# PowerSupply.net
KiCad netlist of a schematic drawn in Altium Designer
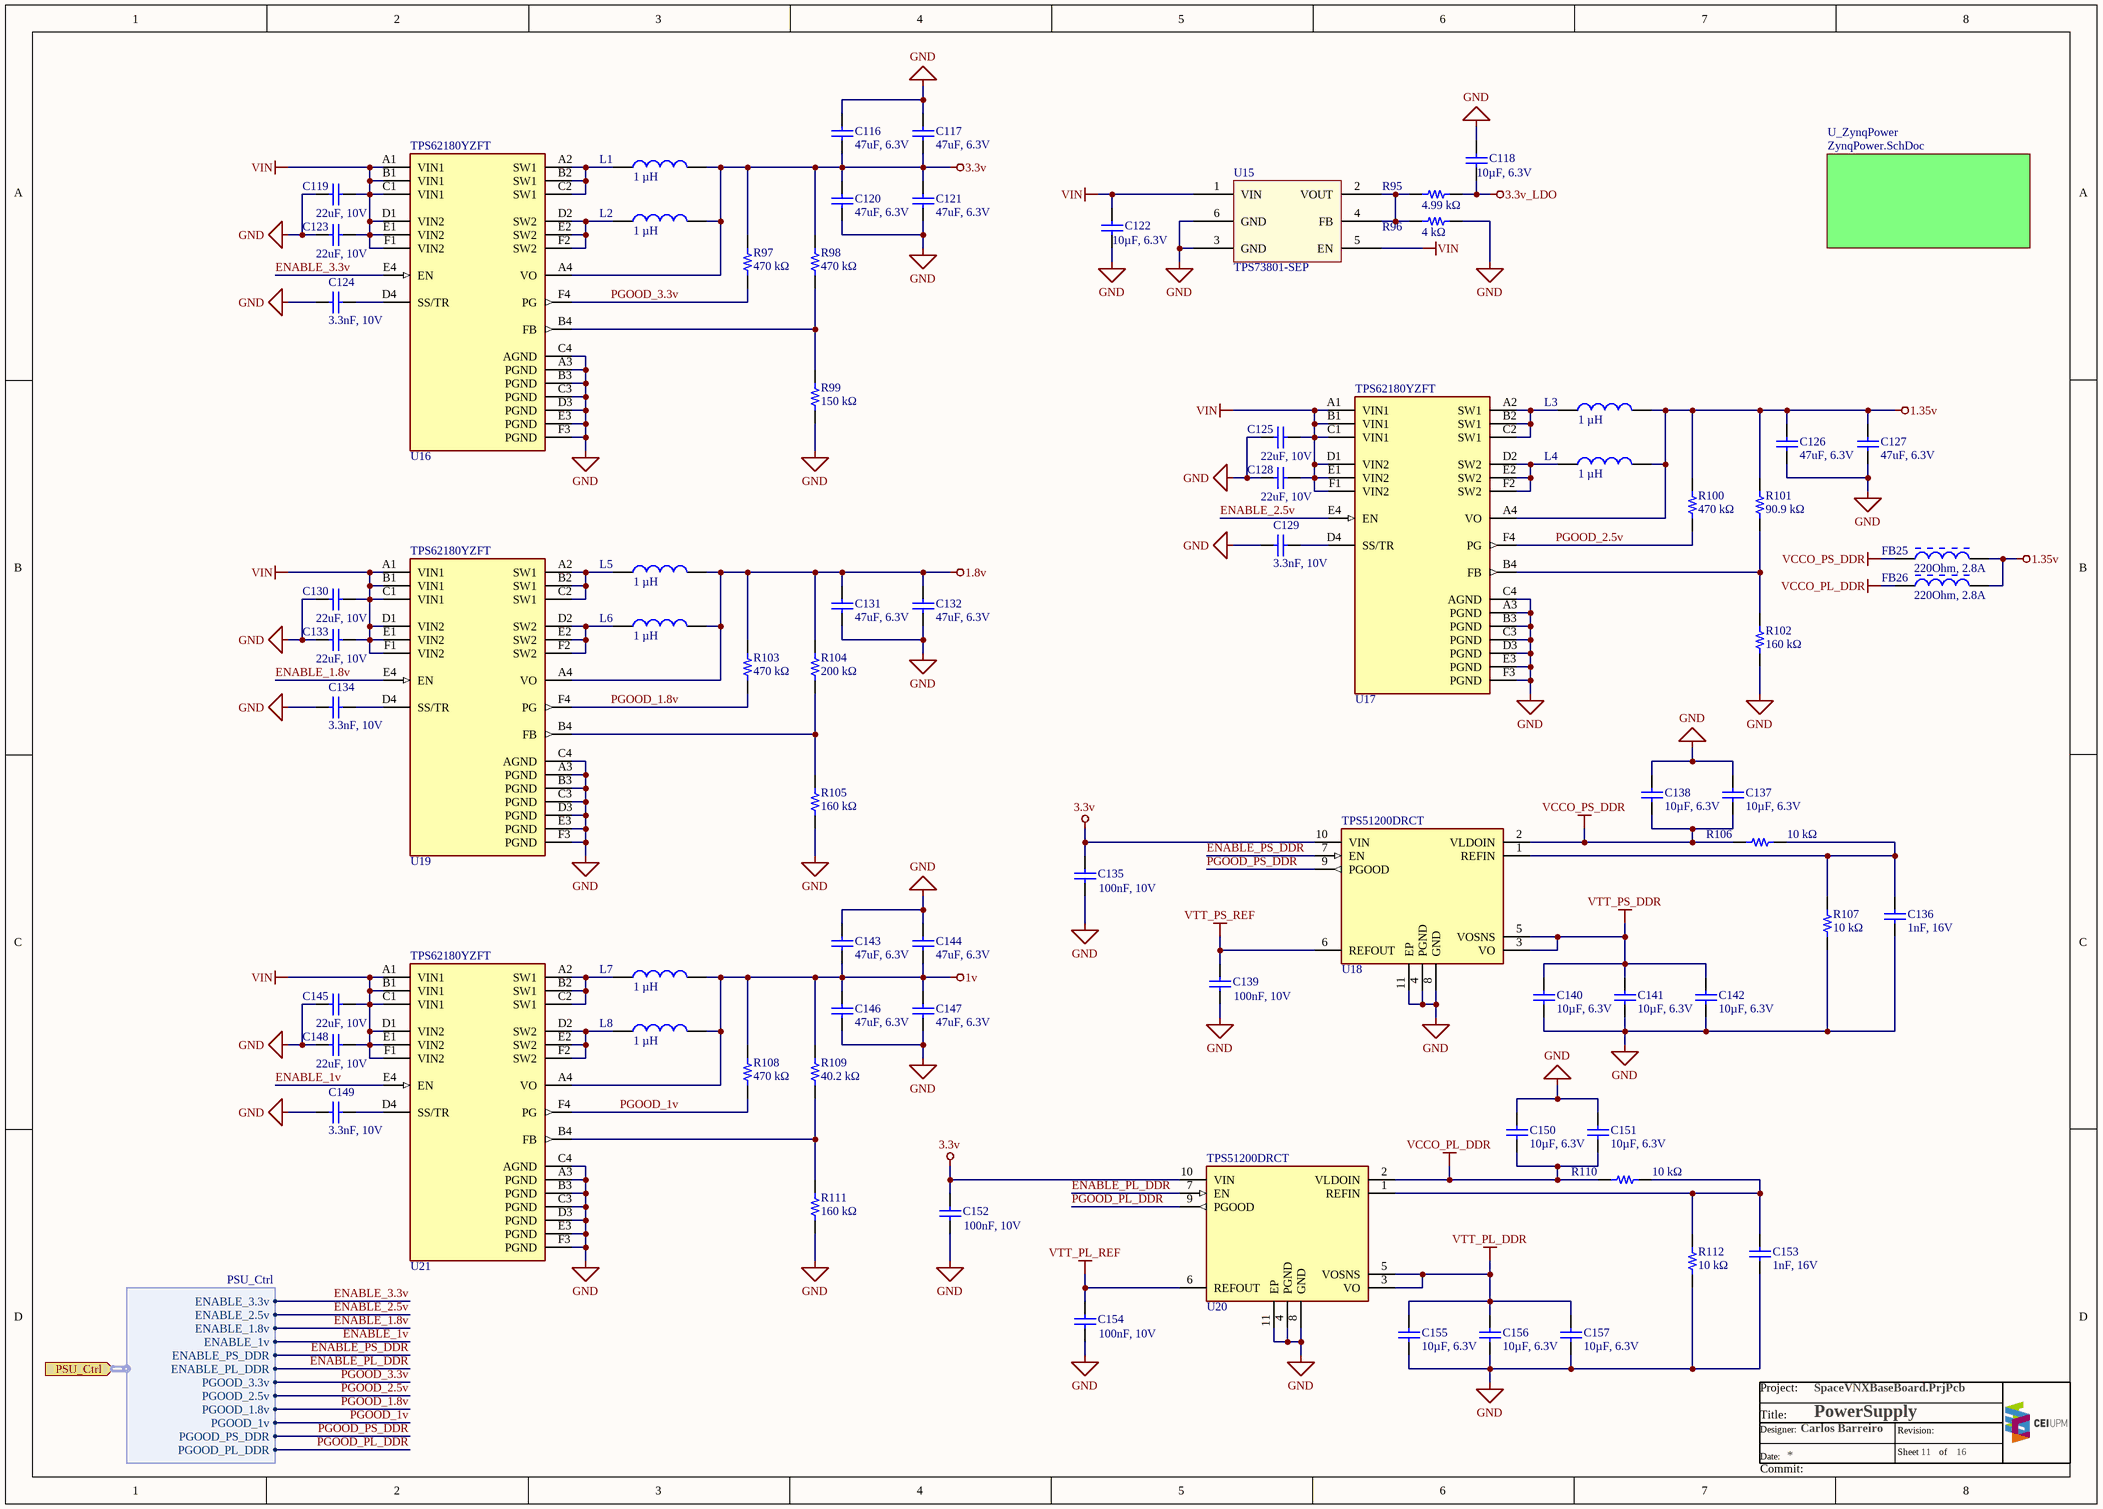
[diagram p0: PowerSupply.SchDoc]

(export (version "E")
  (design (tool "Eeschema 10.0.6"))
  (components
    (comp (ref "C116")
      (value "47uF, 6.3V")
      (footprint "WURTH_WCAP-CSGP_0805_H=1.25mm")
      (description "WCAP-CSGP Multilayer Ceramic Chip Capacitor, General Purpose, size 0805, X5R, 47uF, 6.3V")
      (fields
        (field (name "MANUFACTURER PART NUMBER") "885012107006")
        (field (name "MANUFACTURER") "Wurth Elektronik")
      )
      (libsource (lib "SpaceVNX") (part "885012107006"))
    )
    (comp (ref "C117")
      (value "47uF, 6.3V")
      (footprint "WURTH_WCAP-CSGP_0805_H=1.25mm")
      (description "WCAP-CSGP Multilayer Ceramic Chip Capacitor, General Purpose, size 0805, X5R, 47uF, 6.3V")
      (fields
        (field (name "MANUFACTURER PART NUMBER") "885012107006")
        (field (name "MANUFACTURER") "Wurth Elektronik")
      )
      (libsource (lib "SpaceVNX") (part "885012107006"))
    )
    (comp (ref "C118")
      (value "10µF, 6.3V")
      (footprint "WURTH_WCAP-CSGP_0402")
      (description "WCAP-CSGP Multilayer Ceramic Chip Capacitor, General Purpose, size 0402, X5R, 10uF, 6.3V")
      (fields
        (field (name "MANUFACTURER PART NUMBER") "885012105020")
        (field (name "MANUFACTURER") "Wurth Elektronik")
      )
      (libsource (lib "SpaceVNX") (part "885012105020"))
    )
    (comp (ref "C119")
      (value "22uF, 10V")
      (footprint "WURTH_WCAP-CSGP_0805_H=1.25mm")
      (description "WCAP-CSGP Multilayer Ceramic Chip Capacitor, General Purpose, size 0805, X5R, 22uF, 10V")
      (fields
        (field (name "MANUFACTURER PART NUMBER") "885012107011")
        (field (name "MANUFACTURER") "Wurth Elektronik")
      )
      (libsource (lib "SpaceVNX") (part "885012107011"))
    )
    (comp (ref "C120")
      (value "47uF, 6.3V")
      (footprint "WURTH_WCAP-CSGP_0805_H=1.25mm")
      (description "WCAP-CSGP Multilayer Ceramic Chip Capacitor, General Purpose, size 0805, X5R, 47uF, 6.3V")
      (fields
        (field (name "MANUFACTURER PART NUMBER") "885012107006")
        (field (name "MANUFACTURER") "Wurth Elektronik")
      )
      (libsource (lib "SpaceVNX") (part "885012107006"))
    )
    (comp (ref "C121")
      (value "47uF, 6.3V")
      (footprint "WURTH_WCAP-CSGP_0805_H=1.25mm")
      (description "WCAP-CSGP Multilayer Ceramic Chip Capacitor, General Purpose, size 0805, X5R, 47uF, 6.3V")
      (fields
        (field (name "MANUFACTURER PART NUMBER") "885012107006")
        (field (name "MANUFACTURER") "Wurth Elektronik")
      )
      (libsource (lib "SpaceVNX") (part "885012107006"))
    )
    (comp (ref "C122")
      (value "10µF, 6.3V")
      (footprint "WURTH_WCAP-CSGP_0402")
      (description "WCAP-CSGP Multilayer Ceramic Chip Capacitor, General Purpose, size 0402, X5R, 10uF, 6.3V")
      (fields
        (field (name "MANUFACTURER PART NUMBER") "885012105020")
        (field (name "MANUFACTURER") "Wurth Elektronik")
      )
      (libsource (lib "SpaceVNX") (part "885012105020"))
    )
    (comp (ref "C123")
      (value "22uF, 10V")
      (footprint "WURTH_WCAP-CSGP_0805_H=1.25mm")
      (description "WCAP-CSGP Multilayer Ceramic Chip Capacitor, General Purpose, size 0805, X5R, 22uF, 10V")
      (fields
        (field (name "MANUFACTURER PART NUMBER") "885012107011")
        (field (name "MANUFACTURER") "Wurth Elektronik")
      )
      (libsource (lib "SpaceVNX") (part "885012107011"))
    )
    (comp (ref "C124")
      (value "3.3nF, 10V")
      (footprint "WURTH_WCAP-CSGP_0402")
      (description "WCAP-CSGP Multilayer Ceramic Chip Capacitor, General Purpose, size 0402, X7R, 3.3nF, 10V")
      (fields
        (field (name "MANUFACTURER PART NUMBER") "885012205009")
        (field (name "MANUFACTURER") "Wurth Elektronik")
      )
      (libsource (lib "SpaceVNX") (part "885012205009"))
    )
    (comp (ref "C125")
      (value "22uF, 10V")
      (footprint "WURTH_WCAP-CSGP_0805_H=1.25mm")
      (description "WCAP-CSGP Multilayer Ceramic Chip Capacitor, General Purpose, size 0805, X5R, 22uF, 10V")
      (fields
        (field (name "MANUFACTURER PART NUMBER") "885012107011")
        (field (name "MANUFACTURER") "Wurth Elektronik")
      )
      (libsource (lib "SpaceVNX") (part "885012107011"))
    )
    (comp (ref "C126")
      (value "47uF, 6.3V")
      (footprint "WURTH_WCAP-CSGP_0805_H=1.25mm")
      (description "WCAP-CSGP Multilayer Ceramic Chip Capacitor, General Purpose, size 0805, X5R, 47uF, 6.3V")
      (fields
        (field (name "MANUFACTURER PART NUMBER") "885012107006")
        (field (name "MANUFACTURER") "Wurth Elektronik")
      )
      (libsource (lib "SpaceVNX") (part "885012107006"))
    )
    (comp (ref "C127")
      (value "47uF, 6.3V")
      (footprint "WURTH_WCAP-CSGP_0805_H=1.25mm")
      (description "WCAP-CSGP Multilayer Ceramic Chip Capacitor, General Purpose, size 0805, X5R, 47uF, 6.3V")
      (fields
        (field (name "MANUFACTURER PART NUMBER") "885012107006")
        (field (name "MANUFACTURER") "Wurth Elektronik")
      )
      (libsource (lib "SpaceVNX") (part "885012107006"))
    )
    (comp (ref "C128")
      (value "22uF, 10V")
      (footprint "WURTH_WCAP-CSGP_0805_H=1.25mm")
      (description "WCAP-CSGP Multilayer Ceramic Chip Capacitor, General Purpose, size 0805, X5R, 22uF, 10V")
      (fields
        (field (name "MANUFACTURER PART NUMBER") "885012107011")
        (field (name "MANUFACTURER") "Wurth Elektronik")
      )
      (libsource (lib "SpaceVNX") (part "885012107011"))
    )
    (comp (ref "C129")
      (value "3.3nF, 10V")
      (footprint "WURTH_WCAP-CSGP_0402")
      (description "WCAP-CSGP Multilayer Ceramic Chip Capacitor, General Purpose, size 0402, X7R, 3.3nF, 10V")
      (fields
        (field (name "MANUFACTURER PART NUMBER") "885012205009")
        (field (name "MANUFACTURER") "Wurth Elektronik")
      )
      (libsource (lib "SpaceVNX") (part "885012205009"))
    )
    (comp (ref "C130")
      (value "22uF, 10V")
      (footprint "WURTH_WCAP-CSGP_0805_H=1.25mm")
      (description "WCAP-CSGP Multilayer Ceramic Chip Capacitor, General Purpose, size 0805, X5R, 22uF, 10V")
      (fields
        (field (name "MANUFACTURER PART NUMBER") "885012107011")
        (field (name "MANUFACTURER") "Wurth Elektronik")
      )
      (libsource (lib "SpaceVNX") (part "885012107011"))
    )
    (comp (ref "C131")
      (value "47uF, 6.3V")
      (footprint "WURTH_WCAP-CSGP_0805_H=1.25mm")
      (description "WCAP-CSGP Multilayer Ceramic Chip Capacitor, General Purpose, size 0805, X5R, 47uF, 6.3V")
      (fields
        (field (name "MANUFACTURER PART NUMBER") "885012107006")
        (field (name "MANUFACTURER") "Wurth Elektronik")
      )
      (libsource (lib "SpaceVNX") (part "885012107006"))
    )
    (comp (ref "C132")
      (value "47uF, 6.3V")
      (footprint "WURTH_WCAP-CSGP_0805_H=1.25mm")
      (description "WCAP-CSGP Multilayer Ceramic Chip Capacitor, General Purpose, size 0805, X5R, 47uF, 6.3V")
      (fields
        (field (name "MANUFACTURER PART NUMBER") "885012107006")
        (field (name "MANUFACTURER") "Wurth Elektronik")
      )
      (libsource (lib "SpaceVNX") (part "885012107006"))
    )
    (comp (ref "C133")
      (value "22uF, 10V")
      (footprint "WURTH_WCAP-CSGP_0805_H=1.25mm")
      (description "WCAP-CSGP Multilayer Ceramic Chip Capacitor, General Purpose, size 0805, X5R, 22uF, 10V")
      (fields
        (field (name "MANUFACTURER PART NUMBER") "885012107011")
        (field (name "MANUFACTURER") "Wurth Elektronik")
      )
      (libsource (lib "SpaceVNX") (part "885012107011"))
    )
    (comp (ref "C134")
      (value "3.3nF, 10V")
      (footprint "WURTH_WCAP-CSGP_0402")
      (description "WCAP-CSGP Multilayer Ceramic Chip Capacitor, General Purpose, size 0402, X7R, 3.3nF, 10V")
      (fields
        (field (name "MANUFACTURER PART NUMBER") "885012205009")
        (field (name "MANUFACTURER") "Wurth Elektronik")
      )
      (libsource (lib "SpaceVNX") (part "885012205009"))
    )
    (comp (ref "C135")
      (value "100nF, 10V")
      (footprint "WURTH_WCAP-CSGP_0402")
      (description "WCAP-CSGP Multilayer Ceramic Chip Capacitor, General Purpose, size 0402, X7R, 100nF, 10V")
      (fields
        (field (name "MANUFACTURER PART NUMBER") "885012205018")
        (field (name "MANUFACTURER") "Wurth Elektronik")
      )
      (libsource (lib "SpaceVNX") (part "885012205018"))
    )
    (comp (ref "C136")
      (value "1nF, 16V")
      (footprint "WURTH_WCAP-CSGP_0402")
      (description "WCAP-CSGP Multilayer Ceramic Chip Capacitor, General Purpose, size 0402, X7R, 1nF, 16V")
      (fields
        (field (name "MANUFACTURER PART NUMBER") "885012205025")
        (field (name "MANUFACTURER") "Wurth Elektronik")
      )
      (libsource (lib "SpaceVNX") (part "885012205025"))
    )
    (comp (ref "C137")
      (value "10µF, 6.3V")
      (footprint "WURTH_WCAP-CSGP_0402")
      (description "WCAP-CSGP Multilayer Ceramic Chip Capacitor, General Purpose, size 0402, X5R, 10uF, 6.3V")
      (fields
        (field (name "MANUFACTURER PART NUMBER") "885012105020")
        (field (name "MANUFACTURER") "Wurth Elektronik")
      )
      (libsource (lib "SpaceVNX") (part "885012105020"))
    )
    (comp (ref "C138")
      (value "10µF, 6.3V")
      (footprint "WURTH_WCAP-CSGP_0402")
      (description "WCAP-CSGP Multilayer Ceramic Chip Capacitor, General Purpose, size 0402, X5R, 10uF, 6.3V")
      (fields
        (field (name "MANUFACTURER PART NUMBER") "885012105020")
        (field (name "MANUFACTURER") "Wurth Elektronik")
      )
      (libsource (lib "SpaceVNX") (part "885012105020"))
    )
    (comp (ref "C139")
      (value "100nF, 10V")
      (footprint "WURTH_WCAP-CSGP_0402")
      (description "WCAP-CSGP Multilayer Ceramic Chip Capacitor, General Purpose, size 0402, X7R, 100nF, 10V")
      (fields
        (field (name "MANUFACTURER PART NUMBER") "885012205018")
        (field (name "MANUFACTURER") "Wurth Elektronik")
      )
      (libsource (lib "SpaceVNX") (part "885012205018"))
    )
    (comp (ref "C140")
      (value "10µF, 6.3V")
      (footprint "WURTH_WCAP-CSGP_0402")
      (description "WCAP-CSGP Multilayer Ceramic Chip Capacitor, General Purpose, size 0402, X5R, 10uF, 6.3V")
      (fields
        (field (name "MANUFACTURER PART NUMBER") "885012105020")
        (field (name "MANUFACTURER") "Wurth Elektronik")
      )
      (libsource (lib "SpaceVNX") (part "885012105020"))
    )
    (comp (ref "C141")
      (value "10µF, 6.3V")
      (footprint "WURTH_WCAP-CSGP_0402")
      (description "WCAP-CSGP Multilayer Ceramic Chip Capacitor, General Purpose, size 0402, X5R, 10uF, 6.3V")
      (fields
        (field (name "MANUFACTURER PART NUMBER") "885012105020")
        (field (name "MANUFACTURER") "Wurth Elektronik")
      )
      (libsource (lib "SpaceVNX") (part "885012105020"))
    )
    (comp (ref "C142")
      (value "10µF, 6.3V")
      (footprint "WURTH_WCAP-CSGP_0402")
      (description "WCAP-CSGP Multilayer Ceramic Chip Capacitor, General Purpose, size 0402, X5R, 10uF, 6.3V")
      (fields
        (field (name "MANUFACTURER PART NUMBER") "885012105020")
        (field (name "MANUFACTURER") "Wurth Elektronik")
      )
      (libsource (lib "SpaceVNX") (part "885012105020"))
    )
    (comp (ref "C143")
      (value "47uF, 6.3V")
      (footprint "WURTH_WCAP-CSGP_0805_H=1.25mm")
      (description "WCAP-CSGP Multilayer Ceramic Chip Capacitor, General Purpose, size 0805, X5R, 47uF, 6.3V")
      (fields
        (field (name "MANUFACTURER PART NUMBER") "885012107006")
        (field (name "MANUFACTURER") "Wurth Elektronik")
      )
      (libsource (lib "SpaceVNX") (part "885012107006"))
    )
    (comp (ref "C144")
      (value "47uF, 6.3V")
      (footprint "WURTH_WCAP-CSGP_0805_H=1.25mm")
      (description "WCAP-CSGP Multilayer Ceramic Chip Capacitor, General Purpose, size 0805, X5R, 47uF, 6.3V")
      (fields
        (field (name "MANUFACTURER PART NUMBER") "885012107006")
        (field (name "MANUFACTURER") "Wurth Elektronik")
      )
      (libsource (lib "SpaceVNX") (part "885012107006"))
    )
    (comp (ref "C145")
      (value "22uF, 10V")
      (footprint "WURTH_WCAP-CSGP_0805_H=1.25mm")
      (description "WCAP-CSGP Multilayer Ceramic Chip Capacitor, General Purpose, size 0805, X5R, 22uF, 10V")
      (fields
        (field (name "MANUFACTURER PART NUMBER") "885012107011")
        (field (name "MANUFACTURER") "Wurth Elektronik")
      )
      (libsource (lib "SpaceVNX") (part "885012107011"))
    )
    (comp (ref "C146")
      (value "47uF, 6.3V")
      (footprint "WURTH_WCAP-CSGP_0805_H=1.25mm")
      (description "WCAP-CSGP Multilayer Ceramic Chip Capacitor, General Purpose, size 0805, X5R, 47uF, 6.3V")
      (fields
        (field (name "MANUFACTURER PART NUMBER") "885012107006")
        (field (name "MANUFACTURER") "Wurth Elektronik")
      )
      (libsource (lib "SpaceVNX") (part "885012107006"))
    )
    (comp (ref "C147")
      (value "47uF, 6.3V")
      (footprint "WURTH_WCAP-CSGP_0805_H=1.25mm")
      (description "WCAP-CSGP Multilayer Ceramic Chip Capacitor, General Purpose, size 0805, X5R, 47uF, 6.3V")
      (fields
        (field (name "MANUFACTURER PART NUMBER") "885012107006")
        (field (name "MANUFACTURER") "Wurth Elektronik")
      )
      (libsource (lib "SpaceVNX") (part "885012107006"))
    )
    (comp (ref "C148")
      (value "22uF, 10V")
      (footprint "WURTH_WCAP-CSGP_0805_H=1.25mm")
      (description "WCAP-CSGP Multilayer Ceramic Chip Capacitor, General Purpose, size 0805, X5R, 22uF, 10V")
      (fields
        (field (name "MANUFACTURER PART NUMBER") "885012107011")
        (field (name "MANUFACTURER") "Wurth Elektronik")
      )
      (libsource (lib "SpaceVNX") (part "885012107011"))
    )
    (comp (ref "C149")
      (value "3.3nF, 10V")
      (footprint "WURTH_WCAP-CSGP_0402")
      (description "WCAP-CSGP Multilayer Ceramic Chip Capacitor, General Purpose, size 0402, X7R, 3.3nF, 10V")
      (fields
        (field (name "MANUFACTURER PART NUMBER") "885012205009")
        (field (name "MANUFACTURER") "Wurth Elektronik")
      )
      (libsource (lib "SpaceVNX") (part "885012205009"))
    )
    (comp (ref "C150")
      (value "10µF, 6.3V")
      (footprint "WURTH_WCAP-CSGP_0402")
      (description "WCAP-CSGP Multilayer Ceramic Chip Capacitor, General Purpose, size 0402, X5R, 10uF, 6.3V")
      (fields
        (field (name "MANUFACTURER PART NUMBER") "885012105020")
        (field (name "MANUFACTURER") "Wurth Elektronik")
      )
      (libsource (lib "SpaceVNX") (part "885012105020"))
    )
    (comp (ref "C151")
      (value "10µF, 6.3V")
      (footprint "WURTH_WCAP-CSGP_0402")
      (description "WCAP-CSGP Multilayer Ceramic Chip Capacitor, General Purpose, size 0402, X5R, 10uF, 6.3V")
      (fields
        (field (name "MANUFACTURER PART NUMBER") "885012105020")
        (field (name "MANUFACTURER") "Wurth Elektronik")
      )
      (libsource (lib "SpaceVNX") (part "885012105020"))
    )
    (comp (ref "C152")
      (value "100nF, 10V")
      (footprint "WURTH_WCAP-CSGP_0402")
      (description "WCAP-CSGP Multilayer Ceramic Chip Capacitor, General Purpose, size 0402, X7R, 100nF, 10V")
      (fields
        (field (name "MANUFACTURER PART NUMBER") "885012205018")
        (field (name "MANUFACTURER") "Wurth Elektronik")
      )
      (libsource (lib "SpaceVNX") (part "885012205018"))
    )
    (comp (ref "C153")
      (value "1nF, 16V")
      (footprint "WURTH_WCAP-CSGP_0402")
      (description "WCAP-CSGP Multilayer Ceramic Chip Capacitor, General Purpose, size 0402, X7R, 1nF, 16V")
      (fields
        (field (name "MANUFACTURER PART NUMBER") "885012205025")
        (field (name "MANUFACTURER") "Wurth Elektronik")
      )
      (libsource (lib "SpaceVNX") (part "885012205025"))
    )
    (comp (ref "C154")
      (value "100nF, 10V")
      (footprint "WURTH_WCAP-CSGP_0402")
      (description "WCAP-CSGP Multilayer Ceramic Chip Capacitor, General Purpose, size 0402, X7R, 100nF, 10V")
      (fields
        (field (name "MANUFACTURER PART NUMBER") "885012205018")
        (field (name "MANUFACTURER") "Wurth Elektronik")
      )
      (libsource (lib "SpaceVNX") (part "885012205018"))
    )
    (comp (ref "C155")
      (value "10µF, 6.3V")
      (footprint "WURTH_WCAP-CSGP_0402")
      (description "WCAP-CSGP Multilayer Ceramic Chip Capacitor, General Purpose, size 0402, X5R, 10uF, 6.3V")
      (fields
        (field (name "MANUFACTURER PART NUMBER") "885012105020")
        (field (name "MANUFACTURER") "Wurth Elektronik")
      )
      (libsource (lib "SpaceVNX") (part "885012105020"))
    )
    (comp (ref "C156")
      (value "10µF, 6.3V")
      (footprint "WURTH_WCAP-CSGP_0402")
      (description "WCAP-CSGP Multilayer Ceramic Chip Capacitor, General Purpose, size 0402, X5R, 10uF, 6.3V")
      (fields
        (field (name "MANUFACTURER PART NUMBER") "885012105020")
        (field (name "MANUFACTURER") "Wurth Elektronik")
      )
      (libsource (lib "SpaceVNX") (part "885012105020"))
    )
    (comp (ref "C157")
      (value "10µF, 6.3V")
      (footprint "WURTH_WCAP-CSGP_0402")
      (description "WCAP-CSGP Multilayer Ceramic Chip Capacitor, General Purpose, size 0402, X5R, 10uF, 6.3V")
      (fields
        (field (name "MANUFACTURER PART NUMBER") "885012105020")
        (field (name "MANUFACTURER") "Wurth Elektronik")
      )
      (libsource (lib "SpaceVNX") (part "885012105020"))
    )
    (comp (ref "FB25")
      (value "220Ohm, 2.8A")
      (footprint "WURTH-CBF_0805")
      (description "WE-CBF SMT EMI Suppression Ferrite Bead, size 0805, 220Ohm, 2.8A")
      (fields
        (field (name "MANUFACTURER PART NUMBER") "742792034")
        (field (name "MANUFACTURER") "Wurth Elektronik")
      )
      (libsource (lib "SpaceVNX") (part "742792034"))
    )
    (comp (ref "FB26")
      (value "220Ohm, 2.8A")
      (footprint "WURTH-CBF_0805")
      (description "WE-CBF SMT EMI Suppression Ferrite Bead, size 0805, 220Ohm, 2.8A")
      (fields
        (field (name "MANUFACTURER PART NUMBER") "742792034")
        (field (name "MANUFACTURER") "Wurth Elektronik")
      )
      (libsource (lib "SpaceVNX") (part "742792034"))
    )
    (comp (ref "L1")
      (value "1 µH")
      (footprint "Murata_LQH2HPN_JR")
      (description "Wire Wound Ferrite Inductor")
      (fields (field (name "MANUFACTURER") "Murata"))
      (libsource (lib "SpaceVNX") (part "LQH2HPN1R0NJR"))
    )
    (comp (ref "L2")
      (value "1 µH")
      (footprint "Murata_LQH2HPN_JR")
      (description "Wire Wound Ferrite Inductor")
      (fields (field (name "MANUFACTURER") "Murata"))
      (libsource (lib "SpaceVNX") (part "LQH2HPN1R0NJR"))
    )
    (comp (ref "L3")
      (value "1 µH")
      (footprint "Murata_LQH2HPN_JR")
      (description "Wire Wound Ferrite Inductor")
      (fields (field (name "MANUFACTURER") "Murata"))
      (libsource (lib "SpaceVNX") (part "LQH2HPN1R0NJR"))
    )
    (comp (ref "L4")
      (value "1 µH")
      (footprint "Murata_LQH2HPN_JR")
      (description "Wire Wound Ferrite Inductor")
      (fields (field (name "MANUFACTURER") "Murata"))
      (libsource (lib "SpaceVNX") (part "LQH2HPN1R0NJR"))
    )
    (comp (ref "L5")
      (value "1 µH")
      (footprint "Murata_LQH2HPN_JR")
      (description "Wire Wound Ferrite Inductor")
      (fields (field (name "MANUFACTURER") "Murata"))
      (libsource (lib "SpaceVNX") (part "LQH2HPN1R0NJR"))
    )
    (comp (ref "L6")
      (value "1 µH")
      (footprint "Murata_LQH2HPN_JR")
      (description "Wire Wound Ferrite Inductor")
      (fields (field (name "MANUFACTURER") "Murata"))
      (libsource (lib "SpaceVNX") (part "LQH2HPN1R0NJR"))
    )
    (comp (ref "L7")
      (value "1 µH")
      (footprint "Murata_LQH2HPN_JR")
      (description "Wire Wound Ferrite Inductor")
      (fields (field (name "MANUFACTURER") "Murata"))
      (libsource (lib "SpaceVNX") (part "LQH2HPN1R0NJR"))
    )
    (comp (ref "L8")
      (value "1 µH")
      (footprint "Murata_LQH2HPN_JR")
      (description "Wire Wound Ferrite Inductor")
      (fields (field (name "MANUFACTURER") "Murata"))
      (libsource (lib "SpaceVNX") (part "LQH2HPN1R0NJR"))
    )
    (comp (ref "R95")
      (value "4.99 kΩ")
      (footprint "PANASONIC_ERJ2G_0402")
      (description "General Purpose Thick Film Chip Resistors")
      (fields (field (name "MANUFACTURER") "Panasonic"))
      (libsource (lib "SpaceVNX") (part "ERJ2RKF4991X"))
    )
    (comp (ref "R96")
      (value "4 kΩ")
      (footprint "PANASONIC_ERJ2G_0402")
      (description "General Purpose Thick Film Chip Resistors")
      (fields (field (name "MANUFACTURER") "Panasonic"))
      (libsource (lib "SpaceVNX") (part "ERJ2RKF4021X"))
    )
    (comp (ref "R97")
      (value "470 kΩ")
      (footprint "PANASONIC_ERJ2G_0402")
      (description "General Purpose Thick Film Chip Resistors")
      (fields (field (name "MANUFACTURER") "Panasonic"))
      (libsource (lib "SpaceVNX") (part "ERJ2RKF4703X"))
    )
    (comp (ref "R98")
      (value "470 kΩ")
      (footprint "PANASONIC_ERJ2G_0402")
      (description "General Purpose Thick Film Chip Resistors")
      (fields (field (name "MANUFACTURER") "Panasonic"))
      (libsource (lib "SpaceVNX") (part "ERJ2RKF4703X"))
    )
    (comp (ref "R99")
      (value "150 kΩ")
      (footprint "PANASONIC_ERJ2G_0402")
      (description "General Purpose Thick Film Chip Resistors")
      (fields (field (name "MANUFACTURER") "Panasonic"))
      (libsource (lib "SpaceVNX") (part "ERJ2RKF1503X"))
    )
    (comp (ref "R100")
      (value "470 kΩ")
      (footprint "PANASONIC_ERJ2G_0402")
      (description "General Purpose Thick Film Chip Resistors")
      (fields (field (name "MANUFACTURER") "Panasonic"))
      (libsource (lib "SpaceVNX") (part "ERJ2RKF4703X"))
    )
    (comp (ref "R101")
      (value "90.9 kΩ")
      (footprint "PANASONIC_ERJ2G_0402")
      (description "General Purpose Thick Film Chip Resistors")
      (fields (field (name "MANUFACTURER") "Panasonic"))
      (libsource (lib "SpaceVNX") (part "ERJ2RKF9092X"))
    )
    (comp (ref "R102")
      (value "160 kΩ")
      (footprint "PANASONIC_ERJ2G_0402")
      (description "General Purpose Thick Film Chip Resistors")
      (fields (field (name "MANUFACTURER") "Panasonic"))
      (libsource (lib "SpaceVNX") (part "ERJ2RKF1603X"))
    )
    (comp (ref "R103")
      (value "470 kΩ")
      (footprint "PANASONIC_ERJ2G_0402")
      (description "General Purpose Thick Film Chip Resistors")
      (fields (field (name "MANUFACTURER") "Panasonic"))
      (libsource (lib "SpaceVNX") (part "ERJ2RKF4703X"))
    )
    (comp (ref "R104")
      (value "200 kΩ")
      (footprint "PANASONIC_ERJ2G_0402")
      (description "General Purpose Thick Film Chip Resistors")
      (fields (field (name "MANUFACTURER") "Panasonic"))
      (libsource (lib "SpaceVNX") (part "ERJ2RKF2003X"))
    )
    (comp (ref "R105")
      (value "160 kΩ")
      (footprint "PANASONIC_ERJ2G_0402")
      (description "General Purpose Thick Film Chip Resistors")
      (fields (field (name "MANUFACTURER") "Panasonic"))
      (libsource (lib "SpaceVNX") (part "ERJ2RKF1603X"))
    )
    (comp (ref "R106")
      (value "10 kΩ")
      (footprint "PANASONIC_ERJ2G_0402")
      (description "General Purpose Thick Film Chip Resistors")
      (fields (field (name "MANUFACTURER") "Panasonic"))
      (libsource (lib "SpaceVNX") (part "ERJ2RKF1002X"))
    )
    (comp (ref "R107")
      (value "10 kΩ")
      (footprint "PANASONIC_ERJ2G_0402")
      (description "General Purpose Thick Film Chip Resistors")
      (fields (field (name "MANUFACTURER") "Panasonic"))
      (libsource (lib "SpaceVNX") (part "ERJ2RKF1002X"))
    )
    (comp (ref "R108")
      (value "470 kΩ")
      (footprint "PANASONIC_ERJ2G_0402")
      (description "General Purpose Thick Film Chip Resistors")
      (fields (field (name "MANUFACTURER") "Panasonic"))
      (libsource (lib "SpaceVNX") (part "ERJ2RKF4703X"))
    )
    (comp (ref "R109")
      (value "40.2 kΩ")
      (footprint "PANASONIC_ERJ2G_0402")
      (description "General Purpose Thick Film Chip Resistors")
      (fields (field (name "MANUFACTURER") "Panasonic"))
      (libsource (lib "SpaceVNX") (part "ERJ2RKF4022X"))
    )
    (comp (ref "R110")
      (value "10 kΩ")
      (footprint "PANASONIC_ERJ2G_0402")
      (description "General Purpose Thick Film Chip Resistors")
      (fields (field (name "MANUFACTURER") "Panasonic"))
      (libsource (lib "SpaceVNX") (part "ERJ2RKF1002X"))
    )
    (comp (ref "R111")
      (value "160 kΩ")
      (footprint "PANASONIC_ERJ2G_0402")
      (description "General Purpose Thick Film Chip Resistors")
      (fields (field (name "MANUFACTURER") "Panasonic"))
      (libsource (lib "SpaceVNX") (part "ERJ2RKF1603X"))
    )
    (comp (ref "R112")
      (value "10 kΩ")
      (footprint "PANASONIC_ERJ2G_0402")
      (description "General Purpose Thick Film Chip Resistors")
      (fields (field (name "MANUFACTURER") "Panasonic"))
      (libsource (lib "SpaceVNX") (part "ERJ2RKF1002X"))
    )
    (comp (ref "U15")
      (value "TPS73801-SEP")
      (footprint "TEXAS_SOT223DCQ")
      (description "Radiation-hardened, 2.2-V to 20-V, 1-A low-noise adjustable output LDO in Space Enhanced Plastic")
      (libsource (lib "SpaceVNX") (part "TPS73801-SEP"))
    )
    (comp (ref "U16")
      (value "TPS62180YZFT")
      (footprint "TEXAS_DSBGA24")
      (description "TPS6218x 4-V to 15-V, 6-A, 2-Phase Step-Down Converters")
      (libsource (lib "SpaceVNX") (part "TPS62180YZFT"))
    )
    (comp (ref "U17")
      (value "TPS62180YZFT")
      (footprint "TEXAS_DSBGA24")
      (description "TPS6218x 4-V to 15-V, 6-A, 2-Phase Step-Down Converters")
      (libsource (lib "SpaceVNX") (part "TPS62180YZFT"))
    )
    (comp (ref "U18")
      (value "TPS51200DRCT")
      (footprint "TEXAS_VSON10")
      (fields (field (name "MF") "Texas Instruments"))
      (libsource (lib "SpaceVNX") (part "TPS51200DRCT"))
    )
    (comp (ref "U19")
      (value "TPS62180YZFT")
      (footprint "TEXAS_DSBGA24")
      (description "TPS6218x 4-V to 15-V, 6-A, 2-Phase Step-Down Converters")
      (libsource (lib "SpaceVNX") (part "TPS62180YZFT"))
    )
    (comp (ref "U20")
      (value "TPS51200DRCT")
      (footprint "TEXAS_VSON10")
      (fields (field (name "MF") "Texas Instruments"))
      (libsource (lib "SpaceVNX") (part "TPS51200DRCT"))
    )
    (comp (ref "U21")
      (value "TPS62180YZFT")
      (footprint "TEXAS_DSBGA24")
      (description "TPS6218x 4-V to 15-V, 6-A, 2-Phase Step-Down Converters")
      (libsource (lib "SpaceVNX") (part "TPS62180YZFT"))
    )
  )
  (nets
    (net (code "2") (name "/ENABLE_1.8v") (class "Default")
      (node (ref "U19") (pin "E4") (pinfunction "EN_E4") (pintype "input"))
    )
    (net (code "3") (name "/ENABLE_1v") (class "Default")
      (node (ref "U21") (pin "E4") (pinfunction "EN_E4") (pintype "input"))
    )
    (net (code "4") (name "/ENABLE_2.5v") (class "Default")
      (node (ref "U17") (pin "E4") (pinfunction "EN_E4") (pintype "input"))
    )
    (net (code "5") (name "/ENABLE_3.3v") (class "Default")
      (node (ref "U16") (pin "E4") (pinfunction "EN_E4") (pintype "input"))
    )
    (net (code "6") (name "/ENABLE_PL_DDR") (class "Default")
      (node (ref "U20") (pin "7") (pinfunction "EN_7") (pintype "input"))
    )
    (net (code "7") (name "/ENABLE_PS_DDR") (class "Default")
      (node (ref "U18") (pin "7") (pinfunction "EN_7") (pintype "input"))
    )
    (net (code "8") (name "/PGOOD_1.8v") (class "Default")
      (node (ref "R103") (pin "1") (pinfunction "1_1") (pintype "passive"))
      (node (ref "U19") (pin "F4") (pinfunction "PG_F4") (pintype "output"))
    )
    (net (code "9") (name "/PGOOD_1v") (class "Default")
      (node (ref "R108") (pin "1") (pinfunction "1_1") (pintype "passive"))
      (node (ref "U21") (pin "F4") (pinfunction "PG_F4") (pintype "output"))
    )
    (net (code "10") (name "/PGOOD_2.5v") (class "Default")
      (node (ref "R100") (pin "1") (pinfunction "1_1") (pintype "passive"))
      (node (ref "U17") (pin "F4") (pinfunction "PG_F4") (pintype "output"))
    )
    (net (code "11") (name "/PGOOD_3.3v") (class "Default")
      (node (ref "R97") (pin "1") (pinfunction "1_1") (pintype "passive"))
      (node (ref "U16") (pin "F4") (pinfunction "PG_F4") (pintype "output"))
    )
    (net (code "12") (name "/PGOOD_PL_DDR") (class "Default")
      (node (ref "U20") (pin "9") (pinfunction "PGOOD_9") (pintype "output"))
    )
    (net (code "13") (name "/PGOOD_PS_DDR") (class "Default")
      (node (ref "U18") (pin "9") (pinfunction "PGOOD_9") (pintype "output"))
    )
    (net (code "15") (name "1.8v") (class "Default")
      (node (ref "C131") (pin "2") (pinfunction "2_2") (pintype "passive"))
      (node (ref "C132") (pin "2") (pinfunction "2_2") (pintype "passive"))
      (node (ref "L5") (pin "2") (pinfunction "2_2") (pintype "passive"))
      (node (ref "L6") (pin "2") (pinfunction "2_2") (pintype "passive"))
      (node (ref "R103") (pin "2") (pinfunction "2_2") (pintype "passive"))
      (node (ref "R104") (pin "2") (pinfunction "2_2") (pintype "passive"))
      (node (ref "U19") (pin "A4") (pinfunction "VO_A4") (pintype "power_in"))
    )
    (net (code "16") (name "1.35v") (class "Default")
      (node (ref "C126") (pin "2") (pinfunction "2_2") (pintype "passive"))
      (node (ref "C127") (pin "2") (pinfunction "2_2") (pintype "passive"))
      (node (ref "FB25") (pin "2") (pinfunction "2_2") (pintype "passive"))
      (node (ref "FB26") (pin "2") (pinfunction "2_2") (pintype "passive"))
      (node (ref "L3") (pin "2") (pinfunction "2_2") (pintype "passive"))
      (node (ref "L4") (pin "2") (pinfunction "2_2") (pintype "passive"))
      (node (ref "R100") (pin "2") (pinfunction "2_2") (pintype "passive"))
      (node (ref "R101") (pin "2") (pinfunction "2_2") (pintype "passive"))
      (node (ref "U17") (pin "A4") (pinfunction "VO_A4") (pintype "power_in"))
    )
    (net (code "17") (name "1v") (class "Default")
      (node (ref "C143") (pin "1") (pinfunction "1_1") (pintype "passive"))
      (node (ref "C144") (pin "1") (pinfunction "1_1") (pintype "passive"))
      (node (ref "C146") (pin "2") (pinfunction "2_2") (pintype "passive"))
      (node (ref "C147") (pin "2") (pinfunction "2_2") (pintype "passive"))
      (node (ref "L7") (pin "2") (pinfunction "2_2") (pintype "passive"))
      (node (ref "L8") (pin "2") (pinfunction "2_2") (pintype "passive"))
      (node (ref "R108") (pin "2") (pinfunction "2_2") (pintype "passive"))
      (node (ref "R109") (pin "2") (pinfunction "2_2") (pintype "passive"))
      (node (ref "U21") (pin "A4") (pinfunction "VO_A4") (pintype "power_in"))
    )
    (net (code "18") (name "3.3v") (class "Default")
      (node (ref "C116") (pin "1") (pinfunction "1_1") (pintype "passive"))
      (node (ref "C117") (pin "1") (pinfunction "1_1") (pintype "passive"))
      (node (ref "C120") (pin "2") (pinfunction "2_2") (pintype "passive"))
      (node (ref "C121") (pin "2") (pinfunction "2_2") (pintype "passive"))
      (node (ref "C135") (pin "2") (pinfunction "2_2") (pintype "passive"))
      (node (ref "C152") (pin "2") (pinfunction "2_2") (pintype "passive"))
      (node (ref "L1") (pin "2") (pinfunction "2_2") (pintype "passive"))
      (node (ref "L2") (pin "2") (pinfunction "2_2") (pintype "passive"))
      (node (ref "R97") (pin "2") (pinfunction "2_2") (pintype "passive"))
      (node (ref "R98") (pin "2") (pinfunction "2_2") (pintype "passive"))
      (node (ref "U16") (pin "A4") (pinfunction "VO_A4") (pintype "power_in"))
      (node (ref "U18") (pin "10") (pinfunction "VIN_10") (pintype "passive"))
      (node (ref "U20") (pin "10") (pinfunction "VIN_10") (pintype "passive"))
    )
    (net (code "19") (name "3.3v_LDO") (class "Default")
      (node (ref "C118") (pin "1") (pinfunction "1_1") (pintype "passive"))
      (node (ref "R95") (pin "2") (pinfunction "2_2") (pintype "passive"))
    )
    (net (code "20") (name "GND") (class "Default")
      (node (ref "C116") (pin "2") (pinfunction "2_2") (pintype "passive"))
      (node (ref "C117") (pin "2") (pinfunction "2_2") (pintype "passive"))
      (node (ref "C118") (pin "2") (pinfunction "2_2") (pintype "passive"))
      (node (ref "C119") (pin "2") (pinfunction "2_2") (pintype "passive"))
      (node (ref "C120") (pin "1") (pinfunction "1_1") (pintype "passive"))
      (node (ref "C121") (pin "1") (pinfunction "1_1") (pintype "passive"))
      (node (ref "C122") (pin "1") (pinfunction "1_1") (pintype "passive"))
      (node (ref "C123") (pin "2") (pinfunction "2_2") (pintype "passive"))
      (node (ref "C124") (pin "1") (pinfunction "1_1") (pintype "passive"))
      (node (ref "C125") (pin "2") (pinfunction "2_2") (pintype "passive"))
      (node (ref "C126") (pin "1") (pinfunction "1_1") (pintype "passive"))
      (node (ref "C127") (pin "1") (pinfunction "1_1") (pintype "passive"))
      (node (ref "C128") (pin "2") (pinfunction "2_2") (pintype "passive"))
      (node (ref "C129") (pin "1") (pinfunction "1_1") (pintype "passive"))
      (node (ref "C130") (pin "2") (pinfunction "2_2") (pintype "passive"))
      (node (ref "C131") (pin "1") (pinfunction "1_1") (pintype "passive"))
      (node (ref "C132") (pin "1") (pinfunction "1_1") (pintype "passive"))
      (node (ref "C133") (pin "2") (pinfunction "2_2") (pintype "passive"))
      (node (ref "C134") (pin "1") (pinfunction "1_1") (pintype "passive"))
      (node (ref "C135") (pin "1") (pinfunction "1_1") (pintype "passive"))
      (node (ref "C136") (pin "2") (pinfunction "2_2") (pintype "passive"))
      (node (ref "C137") (pin "1") (pinfunction "1_1") (pintype "passive"))
      (node (ref "C138") (pin "1") (pinfunction "1_1") (pintype "passive"))
      (node (ref "C139") (pin "1") (pinfunction "1_1") (pintype "passive"))
      (node (ref "C140") (pin "1") (pinfunction "1_1") (pintype "passive"))
      (node (ref "C141") (pin "1") (pinfunction "1_1") (pintype "passive"))
      (node (ref "C142") (pin "1") (pinfunction "1_1") (pintype "passive"))
      (node (ref "C143") (pin "2") (pinfunction "2_2") (pintype "passive"))
      (node (ref "C144") (pin "2") (pinfunction "2_2") (pintype "passive"))
      (node (ref "C145") (pin "2") (pinfunction "2_2") (pintype "passive"))
      (node (ref "C146") (pin "1") (pinfunction "1_1") (pintype "passive"))
      (node (ref "C147") (pin "1") (pinfunction "1_1") (pintype "passive"))
      (node (ref "C148") (pin "2") (pinfunction "2_2") (pintype "passive"))
      (node (ref "C149") (pin "1") (pinfunction "1_1") (pintype "passive"))
      (node (ref "C150") (pin "1") (pinfunction "1_1") (pintype "passive"))
      (node (ref "C151") (pin "1") (pinfunction "1_1") (pintype "passive"))
      (node (ref "C152") (pin "1") (pinfunction "1_1") (pintype "passive"))
      (node (ref "C153") (pin "2") (pinfunction "2_2") (pintype "passive"))
      (node (ref "C154") (pin "1") (pinfunction "1_1") (pintype "passive"))
      (node (ref "C155") (pin "1") (pinfunction "1_1") (pintype "passive"))
      (node (ref "C156") (pin "1") (pinfunction "1_1") (pintype "passive"))
      (node (ref "C157") (pin "1") (pinfunction "1_1") (pintype "passive"))
      (node (ref "R102") (pin "1") (pinfunction "1_1") (pintype "passive"))
      (node (ref "R105") (pin "1") (pinfunction "1_1") (pintype "passive"))
      (node (ref "R107") (pin "1") (pinfunction "1_1") (pintype "passive"))
      (node (ref "R111") (pin "1") (pinfunction "1_1") (pintype "passive"))
      (node (ref "R112") (pin "1") (pinfunction "1_1") (pintype "passive"))
      (node (ref "R96") (pin "2") (pinfunction "2_2") (pintype "passive"))
      (node (ref "R99") (pin "1") (pinfunction "1_1") (pintype "passive"))
      (node (ref "U15") (pin "3") (pinfunction "GND_3") (pintype "passive"))
      (node (ref "U15") (pin "6") (pinfunction "GND_6") (pintype "passive"))
      (node (ref "U16") (pin "A3") (pinfunction "PGND_A3") (pintype "power_in"))
      (node (ref "U16") (pin "B3") (pinfunction "PGND_B3") (pintype "power_in"))
      (node (ref "U16") (pin "C3") (pinfunction "PGND_C3") (pintype "power_in"))
      (node (ref "U16") (pin "C4") (pinfunction "AGND_C4") (pintype "power_in"))
      (node (ref "U16") (pin "D3") (pinfunction "PGND_D3") (pintype "power_in"))
      (node (ref "U16") (pin "E3") (pinfunction "PGND_E3") (pintype "power_in"))
      (node (ref "U16") (pin "F3") (pinfunction "PGND_F3") (pintype "power_in"))
      (node (ref "U17") (pin "A3") (pinfunction "PGND_A3") (pintype "power_in"))
      (node (ref "U17") (pin "B3") (pinfunction "PGND_B3") (pintype "power_in"))
      (node (ref "U17") (pin "C3") (pinfunction "PGND_C3") (pintype "power_in"))
      (node (ref "U17") (pin "C4") (pinfunction "AGND_C4") (pintype "power_in"))
      (node (ref "U17") (pin "D3") (pinfunction "PGND_D3") (pintype "power_in"))
      (node (ref "U17") (pin "E3") (pinfunction "PGND_E3") (pintype "power_in"))
      (node (ref "U17") (pin "F3") (pinfunction "PGND_F3") (pintype "power_in"))
      (node (ref "U18") (pin "11") (pinfunction "EP_11") (pintype "power_in"))
      (node (ref "U18") (pin "4") (pinfunction "PGND_4") (pintype "power_in"))
      (node (ref "U18") (pin "8") (pinfunction "GND_8") (pintype "power_in"))
      (node (ref "U19") (pin "A3") (pinfunction "PGND_A3") (pintype "power_in"))
      (node (ref "U19") (pin "B3") (pinfunction "PGND_B3") (pintype "power_in"))
      (node (ref "U19") (pin "C3") (pinfunction "PGND_C3") (pintype "power_in"))
      (node (ref "U19") (pin "C4") (pinfunction "AGND_C4") (pintype "power_in"))
      (node (ref "U19") (pin "D3") (pinfunction "PGND_D3") (pintype "power_in"))
      (node (ref "U19") (pin "E3") (pinfunction "PGND_E3") (pintype "power_in"))
      (node (ref "U19") (pin "F3") (pinfunction "PGND_F3") (pintype "power_in"))
      (node (ref "U20") (pin "11") (pinfunction "EP_11") (pintype "power_in"))
      (node (ref "U20") (pin "4") (pinfunction "PGND_4") (pintype "power_in"))
      (node (ref "U20") (pin "8") (pinfunction "GND_8") (pintype "power_in"))
      (node (ref "U21") (pin "A3") (pinfunction "PGND_A3") (pintype "power_in"))
      (node (ref "U21") (pin "B3") (pinfunction "PGND_B3") (pintype "power_in"))
      (node (ref "U21") (pin "C3") (pinfunction "PGND_C3") (pintype "power_in"))
      (node (ref "U21") (pin "C4") (pinfunction "AGND_C4") (pintype "power_in"))
      (node (ref "U21") (pin "D3") (pinfunction "PGND_D3") (pintype "power_in"))
      (node (ref "U21") (pin "E3") (pinfunction "PGND_E3") (pintype "power_in"))
      (node (ref "U21") (pin "F3") (pinfunction "PGND_F3") (pintype "power_in"))
    )
    (net (code "21") (name "Net-(L1-Pad1)") (class "Default")
      (node (ref "L1") (pin "1") (pinfunction "1_1") (pintype "passive"))
      (node (ref "U16") (pin "A2") (pinfunction "SW1_A2") (pintype "passive"))
      (node (ref "U16") (pin "B2") (pinfunction "SW1_B2") (pintype "passive"))
      (node (ref "U16") (pin "C2") (pinfunction "SW1_C2") (pintype "passive"))
    )
    (net (code "22") (name "Net-(L2-Pad1)") (class "Default")
      (node (ref "L2") (pin "1") (pinfunction "1_1") (pintype "passive"))
      (node (ref "U16") (pin "D2") (pinfunction "SW2_D2") (pintype "passive"))
      (node (ref "U16") (pin "E2") (pinfunction "SW2_E2") (pintype "passive"))
      (node (ref "U16") (pin "F2") (pinfunction "SW2_F2") (pintype "passive"))
    )
    (net (code "23") (name "Net-(L3-Pad1)") (class "Default")
      (node (ref "L3") (pin "1") (pinfunction "1_1") (pintype "passive"))
      (node (ref "U17") (pin "A2") (pinfunction "SW1_A2") (pintype "passive"))
      (node (ref "U17") (pin "B2") (pinfunction "SW1_B2") (pintype "passive"))
      (node (ref "U17") (pin "C2") (pinfunction "SW1_C2") (pintype "passive"))
    )
    (net (code "24") (name "Net-(L4-Pad1)") (class "Default")
      (node (ref "L4") (pin "1") (pinfunction "1_1") (pintype "passive"))
      (node (ref "U17") (pin "D2") (pinfunction "SW2_D2") (pintype "passive"))
      (node (ref "U17") (pin "E2") (pinfunction "SW2_E2") (pintype "passive"))
      (node (ref "U17") (pin "F2") (pinfunction "SW2_F2") (pintype "passive"))
    )
    (net (code "25") (name "Net-(L5-Pad1)") (class "Default")
      (node (ref "L5") (pin "1") (pinfunction "1_1") (pintype "passive"))
      (node (ref "U19") (pin "A2") (pinfunction "SW1_A2") (pintype "passive"))
      (node (ref "U19") (pin "B2") (pinfunction "SW1_B2") (pintype "passive"))
      (node (ref "U19") (pin "C2") (pinfunction "SW1_C2") (pintype "passive"))
    )
    (net (code "26") (name "Net-(L6-Pad1)") (class "Default")
      (node (ref "L6") (pin "1") (pinfunction "1_1") (pintype "passive"))
      (node (ref "U19") (pin "D2") (pinfunction "SW2_D2") (pintype "passive"))
      (node (ref "U19") (pin "E2") (pinfunction "SW2_E2") (pintype "passive"))
      (node (ref "U19") (pin "F2") (pinfunction "SW2_F2") (pintype "passive"))
    )
    (net (code "27") (name "Net-(L7-Pad1)") (class "Default")
      (node (ref "L7") (pin "1") (pinfunction "1_1") (pintype "passive"))
      (node (ref "U21") (pin "A2") (pinfunction "SW1_A2") (pintype "passive"))
      (node (ref "U21") (pin "B2") (pinfunction "SW1_B2") (pintype "passive"))
      (node (ref "U21") (pin "C2") (pinfunction "SW1_C2") (pintype "passive"))
    )
    (net (code "28") (name "Net-(L8-Pad1)") (class "Default")
      (node (ref "L8") (pin "1") (pinfunction "1_1") (pintype "passive"))
      (node (ref "U21") (pin "D2") (pinfunction "SW2_D2") (pintype "passive"))
      (node (ref "U21") (pin "E2") (pinfunction "SW2_E2") (pintype "passive"))
      (node (ref "U21") (pin "F2") (pinfunction "SW2_F2") (pintype "passive"))
    )
    (net (code "29") (name "Net-(U15-FB)") (class "Default")
      (node (ref "R95") (pin "1") (pinfunction "1_1") (pintype "passive"))
      (node (ref "R96") (pin "1") (pinfunction "1_1") (pintype "passive"))
      (node (ref "U15") (pin "2") (pinfunction "VOUT_2") (pintype "passive"))
      (node (ref "U15") (pin "4") (pinfunction "FB_4") (pintype "passive"))
    )
    (net (code "30") (name "Net-(U16-FB)") (class "Default")
      (node (ref "R98") (pin "1") (pinfunction "1_1") (pintype "passive"))
      (node (ref "R99") (pin "2") (pinfunction "2_2") (pintype "passive"))
      (node (ref "U16") (pin "B4") (pinfunction "FB_B4") (pintype "output"))
    )
    (net (code "31") (name "Net-(U16-SS{slash}TR)") (class "Default")
      (node (ref "C124") (pin "2") (pinfunction "2_2") (pintype "passive"))
      (node (ref "U16") (pin "D4") (pinfunction "SS/TR_D4") (pintype "passive"))
    )
    (net (code "32") (name "Net-(U17-FB)") (class "Default")
      (node (ref "R101") (pin "1") (pinfunction "1_1") (pintype "passive"))
      (node (ref "R102") (pin "2") (pinfunction "2_2") (pintype "passive"))
      (node (ref "U17") (pin "B4") (pinfunction "FB_B4") (pintype "output"))
    )
    (net (code "33") (name "Net-(U17-SS{slash}TR)") (class "Default")
      (node (ref "C129") (pin "2") (pinfunction "2_2") (pintype "passive"))
      (node (ref "U17") (pin "D4") (pinfunction "SS/TR_D4") (pintype "passive"))
    )
    (net (code "34") (name "Net-(U18-REFIN)") (class "Default")
      (node (ref "C136") (pin "1") (pinfunction "1_1") (pintype "passive"))
      (node (ref "R106") (pin "2") (pinfunction "2_2") (pintype "passive"))
      (node (ref "R107") (pin "2") (pinfunction "2_2") (pintype "passive"))
      (node (ref "U18") (pin "1") (pinfunction "REFIN_1") (pintype "passive"))
    )
    (net (code "35") (name "Net-(U19-FB)") (class "Default")
      (node (ref "R104") (pin "1") (pinfunction "1_1") (pintype "passive"))
      (node (ref "R105") (pin "2") (pinfunction "2_2") (pintype "passive"))
      (node (ref "U19") (pin "B4") (pinfunction "FB_B4") (pintype "output"))
    )
    (net (code "36") (name "Net-(U19-SS{slash}TR)") (class "Default")
      (node (ref "C134") (pin "2") (pinfunction "2_2") (pintype "passive"))
      (node (ref "U19") (pin "D4") (pinfunction "SS/TR_D4") (pintype "passive"))
    )
    (net (code "37") (name "Net-(U20-REFIN)") (class "Default")
      (node (ref "C153") (pin "1") (pinfunction "1_1") (pintype "passive"))
      (node (ref "R110") (pin "2") (pinfunction "2_2") (pintype "passive"))
      (node (ref "R112") (pin "2") (pinfunction "2_2") (pintype "passive"))
      (node (ref "U20") (pin "1") (pinfunction "REFIN_1") (pintype "passive"))
    )
    (net (code "38") (name "Net-(U21-FB)") (class "Default")
      (node (ref "R109") (pin "1") (pinfunction "1_1") (pintype "passive"))
      (node (ref "R111") (pin "2") (pinfunction "2_2") (pintype "passive"))
      (node (ref "U21") (pin "B4") (pinfunction "FB_B4") (pintype "output"))
    )
    (net (code "39") (name "Net-(U21-SS{slash}TR)") (class "Default")
      (node (ref "C149") (pin "2") (pinfunction "2_2") (pintype "passive"))
      (node (ref "U21") (pin "D4") (pinfunction "SS/TR_D4") (pintype "passive"))
    )
    (net (code "40") (name "VCCO_PL_DDR") (class "Default")
      (node (ref "C150") (pin "2") (pinfunction "2_2") (pintype "passive"))
      (node (ref "C151") (pin "2") (pinfunction "2_2") (pintype "passive"))
      (node (ref "FB26") (pin "1") (pinfunction "1_1") (pintype "passive"))
      (node (ref "R110") (pin "1") (pinfunction "1_1") (pintype "passive"))
      (node (ref "U20") (pin "2") (pinfunction "VLDOIN_2") (pintype "passive"))
    )
    (net (code "41") (name "VCCO_PS_DDR") (class "Default")
      (node (ref "C137") (pin "2") (pinfunction "2_2") (pintype "passive"))
      (node (ref "C138") (pin "2") (pinfunction "2_2") (pintype "passive"))
      (node (ref "FB25") (pin "1") (pinfunction "1_1") (pintype "passive"))
      (node (ref "R106") (pin "1") (pinfunction "1_1") (pintype "passive"))
      (node (ref "U18") (pin "2") (pinfunction "VLDOIN_2") (pintype "passive"))
    )
    (net (code "42") (name "VIN") (class "Default")
      (node (ref "C119") (pin "1") (pinfunction "1_1") (pintype "passive"))
      (node (ref "C122") (pin "2") (pinfunction "2_2") (pintype "passive"))
      (node (ref "C123") (pin "1") (pinfunction "1_1") (pintype "passive"))
      (node (ref "C125") (pin "1") (pinfunction "1_1") (pintype "passive"))
      (node (ref "C128") (pin "1") (pinfunction "1_1") (pintype "passive"))
      (node (ref "C130") (pin "1") (pinfunction "1_1") (pintype "passive"))
      (node (ref "C133") (pin "1") (pinfunction "1_1") (pintype "passive"))
      (node (ref "C145") (pin "1") (pinfunction "1_1") (pintype "passive"))
      (node (ref "C148") (pin "1") (pinfunction "1_1") (pintype "passive"))
      (node (ref "U15") (pin "1") (pinfunction "VIN_1") (pintype "passive"))
      (node (ref "U15") (pin "5") (pinfunction "EN_5") (pintype "passive"))
      (node (ref "U16") (pin "A1") (pinfunction "VIN1_A1") (pintype "power_in"))
      (node (ref "U16") (pin "B1") (pinfunction "VIN1_B1") (pintype "power_in"))
      (node (ref "U16") (pin "C1") (pinfunction "VIN1_C1") (pintype "power_in"))
      (node (ref "U16") (pin "D1") (pinfunction "VIN2_D1") (pintype "power_in"))
      (node (ref "U16") (pin "E1") (pinfunction "VIN2_E1") (pintype "power_in"))
      (node (ref "U16") (pin "F1") (pinfunction "VIN2_F1") (pintype "power_in"))
      (node (ref "U17") (pin "A1") (pinfunction "VIN1_A1") (pintype "power_in"))
      (node (ref "U17") (pin "B1") (pinfunction "VIN1_B1") (pintype "power_in"))
      (node (ref "U17") (pin "C1") (pinfunction "VIN1_C1") (pintype "power_in"))
      (node (ref "U17") (pin "D1") (pinfunction "VIN2_D1") (pintype "power_in"))
      (node (ref "U17") (pin "E1") (pinfunction "VIN2_E1") (pintype "power_in"))
      (node (ref "U17") (pin "F1") (pinfunction "VIN2_F1") (pintype "power_in"))
      (node (ref "U19") (pin "A1") (pinfunction "VIN1_A1") (pintype "power_in"))
      (node (ref "U19") (pin "B1") (pinfunction "VIN1_B1") (pintype "power_in"))
      (node (ref "U19") (pin "C1") (pinfunction "VIN1_C1") (pintype "power_in"))
      (node (ref "U19") (pin "D1") (pinfunction "VIN2_D1") (pintype "power_in"))
      (node (ref "U19") (pin "E1") (pinfunction "VIN2_E1") (pintype "power_in"))
      (node (ref "U19") (pin "F1") (pinfunction "VIN2_F1") (pintype "power_in"))
      (node (ref "U21") (pin "A1") (pinfunction "VIN1_A1") (pintype "power_in"))
      (node (ref "U21") (pin "B1") (pinfunction "VIN1_B1") (pintype "power_in"))
      (node (ref "U21") (pin "C1") (pinfunction "VIN1_C1") (pintype "power_in"))
      (node (ref "U21") (pin "D1") (pinfunction "VIN2_D1") (pintype "power_in"))
      (node (ref "U21") (pin "E1") (pinfunction "VIN2_E1") (pintype "power_in"))
      (node (ref "U21") (pin "F1") (pinfunction "VIN2_F1") (pintype "power_in"))
    )
    (net (code "43") (name "VTT_PL_DDR") (class "Default")
      (node (ref "C155") (pin "2") (pinfunction "2_2") (pintype "passive"))
      (node (ref "C156") (pin "2") (pinfunction "2_2") (pintype "passive"))
      (node (ref "C157") (pin "2") (pinfunction "2_2") (pintype "passive"))
      (node (ref "U20") (pin "3") (pinfunction "VO_3") (pintype "passive"))
      (node (ref "U20") (pin "5") (pinfunction "VOSNS_5") (pintype "passive"))
    )
    (net (code "44") (name "VTT_PL_REF") (class "Default")
      (node (ref "C154") (pin "2") (pinfunction "2_2") (pintype "passive"))
      (node (ref "U20") (pin "6") (pinfunction "REFOUT_6") (pintype "passive"))
    )
    (net (code "45") (name "VTT_PS_DDR") (class "Default")
      (node (ref "C140") (pin "2") (pinfunction "2_2") (pintype "passive"))
      (node (ref "C141") (pin "2") (pinfunction "2_2") (pintype "passive"))
      (node (ref "C142") (pin "2") (pinfunction "2_2") (pintype "passive"))
      (node (ref "U18") (pin "3") (pinfunction "VO_3") (pintype "passive"))
      (node (ref "U18") (pin "5") (pinfunction "VOSNS_5") (pintype "passive"))
    )
    (net (code "46") (name "VTT_PS_REF") (class "Default")
      (node (ref "C139") (pin "2") (pinfunction "2_2") (pintype "passive"))
      (node (ref "U18") (pin "6") (pinfunction "REFOUT_6") (pintype "passive"))
    )
  )
)
